# PIR.net
KiCad netlist of a schematic drawn in Altium Designer
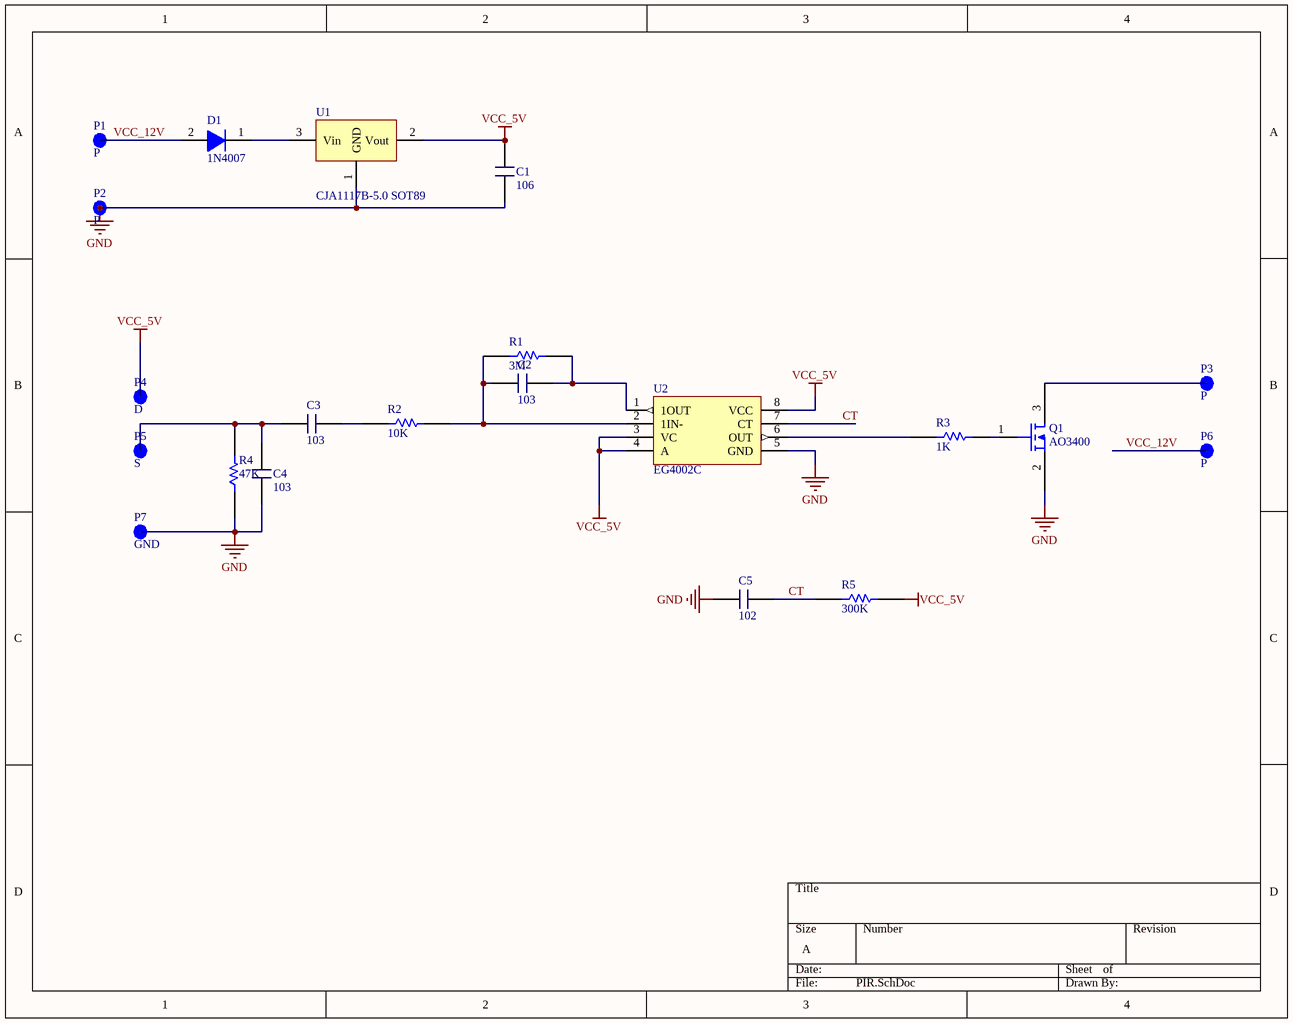
[diagram p0: PIR.SchDoc]

(export (version "E")
  (design (tool "Eeschema 10.0.6"))
  (components
    (comp (ref "C1")
      (value "106")
      (footprint "CAPC2012X12N")
      (libsource (lib "Integrated_Library1") (part "Capacitor 106"))
    )
    (comp (ref "C2")
      (value "103")
      (footprint "CAPC2012X12N")
      (libsource (lib "Integrated_Library1") (part "Capacitor 103 0603"))
    )
    (comp (ref "C3")
      (value "103")
      (footprint "CAPC2012X12N")
      (libsource (lib "Integrated_Library1") (part "Capacitor 103 0603"))
    )
    (comp (ref "C4")
      (value "103")
      (footprint "CAPC2012X12N")
      (libsource (lib "Integrated_Library1") (part "Capacitor 103 0603"))
    )
    (comp (ref "C5")
      (value "102")
      (footprint "CAPC2012X12N")
      (libsource (lib "Integrated_Library1") (part "Capacitor 102 0603"))
    )
    (comp (ref "D1")
      (value "1N4007")
      (footprint "SODFL504X244-2N")
      (description "1N4007_SMD")
      (libsource (lib "Integrated_Library1") (part "1N4007_SMD Diode"))
    )
    (comp (ref "P1") (value "P") (footprint "Point") (libsource (lib "Integrated_Library1") (part "Point")))
    (comp (ref "P2") (value "P") (footprint "Point") (libsource (lib "Integrated_Library1") (part "Point")))
    (comp (ref "P3") (value "P") (footprint "Point") (libsource (lib "Integrated_Library1") (part "Point")))
    (comp (ref "P4") (value "D") (footprint "Point") (libsource (lib "Integrated_Library1") (part "Point")))
    (comp (ref "P5") (value "S") (footprint "Point") (libsource (lib "Integrated_Library1") (part "Point")))
    (comp (ref "P6") (value "P") (footprint "Point") (libsource (lib "Integrated_Library1") (part "Point")))
    (comp (ref "P7") (value "GND") (footprint "Point") (libsource (lib "Integrated_Library1") (part "Point")))
    (comp (ref "Q1")
      (value "AO3400")
      (footprint "SOT95P278X125-3N")
      (description "AO3400  MOSFET SOT23-3")
      (libsource (lib "Integrated_Library1") (part "AO3400  MOSFET SOT23-3"))
    )
    (comp (ref "R1")
      (value "3M")
      (footprint "RESC2608X06N_0603")
      (description "Thick Film Resistors - SMD 0603 3MOHMS 5% 1/10WATT")
      (libsource (lib "Integrated_Library1") (part "3M_0603_5%"))
    )
    (comp (ref "R2")
      (value "10K")
      (footprint "RESC2608X06N_0603")
      (description "RES SMD 10K OHM 1% 1/4W 0603")
      (libsource (lib "Integrated_Library1") (part "R10k_0603_5%"))
    )
    (comp (ref "R3")
      (value "1K")
      (footprint "RESC2608X06N_0603")
      (description "Thick Film Resistors - SMD 0603 1kOHMS 5% 1/10WATT")
      (libsource (lib "Integrated_Library1") (part "1k_0603_5%"))
    )
    (comp (ref "R4")
      (value "47K")
      (footprint "RESC2608X06N_0603")
      (description "Thick Film Resistors - SMD 0603 47kOHMS 5% 1/10WATT")
      (libsource (lib "Integrated_Library1") (part "47k_0603_5%"))
    )
    (comp (ref "R5")
      (value "300K")
      (footprint "RESC2608X06N_0603")
      (description "Thick Film Resistors - SMD 0603 300kOHMS 5% 1/10WATT")
      (libsource (lib "Integrated_Library1") (part "300k_0603_5%"))
    )
    (comp (ref "U1")
      (value "CJA1117B-5.0 SOT89")
      (footprint "SOT89-150P409X160-3N")
      (description "CJA1117B-5.0 SOT89 Power IC 1A 5V_IC")
      (libsource (lib "Integrated_Library1") (part "CJA1117B-5.0 SOT89"))
    )
    (comp (ref "U2")
      (value "EG4002C")
      (footprint "TSOP127P620X155-8N")
      (description "IC PIR CONTROLLER8SOIC")
      (libsource (lib "Integrated_Library1") (part "EG4002C"))
    )
  )
  (nets
    (net (code "1") (name "/CT") (class "Default")
      (node (ref "C5") (pin "2") (pinfunction "2_2") (pintype "passive"))
      (node (ref "R5") (pin "1") (pinfunction "1_1") (pintype "passive"))
      (node (ref "U2") (pin "7") (pinfunction "CT_7") (pintype "passive"))
    )
    (net (code "2") (name "/VCC_12V") (class "Default")
      (node (ref "D1") (pin "2") (pinfunction "A_2") (pintype "passive"))
      (node (ref "P1") (pin "1") (pinfunction "1_1") (pintype "passive"))
      (node (ref "P6") (pin "1") (pinfunction "1_1") (pintype "passive"))
    )
    (net (code "3") (name "GND") (class "Default")
      (node (ref "C1") (pin "1") (pinfunction "1_1") (pintype "passive"))
      (node (ref "C4") (pin "1") (pinfunction "1_1") (pintype "passive"))
      (node (ref "C5") (pin "1") (pinfunction "1_1") (pintype "passive"))
      (node (ref "P2") (pin "1") (pinfunction "1_1") (pintype "passive"))
      (node (ref "P7") (pin "1") (pinfunction "1_1") (pintype "passive"))
      (node (ref "Q1") (pin "2") (pinfunction "S_2") (pintype "passive"))
      (node (ref "R4") (pin "1") (pinfunction "1_1") (pintype "passive"))
      (node (ref "U1") (pin "1") (pinfunction "GND_1") (pintype "power_in"))
      (node (ref "U2") (pin "5") (pinfunction "GND_5") (pintype "power_in"))
    )
    (net (code "4") (name "Net-(C3-Pad1)") (class "Default")
      (node (ref "C3") (pin "1") (pinfunction "1_1") (pintype "passive"))
      (node (ref "R2") (pin "1") (pinfunction "1_1") (pintype "passive"))
    )
    (net (code "5") (name "Net-(C3-Pad2)") (class "Default")
      (node (ref "C3") (pin "2") (pinfunction "2_2") (pintype "passive"))
      (node (ref "C4") (pin "2") (pinfunction "2_2") (pintype "passive"))
      (node (ref "P5") (pin "1") (pinfunction "1_1") (pintype "passive"))
      (node (ref "R4") (pin "2") (pinfunction "2_2") (pintype "passive"))
    )
    (net (code "6") (name "Net-(D1-C)") (class "Default")
      (node (ref "D1") (pin "1") (pinfunction "C_1") (pintype "passive"))
      (node (ref "U1") (pin "3") (pinfunction "Vin_3") (pintype "power_in"))
    )
    (net (code "7") (name "Net-(Q1-D)") (class "Default")
      (node (ref "P3") (pin "1") (pinfunction "1_1") (pintype "passive"))
      (node (ref "Q1") (pin "3") (pinfunction "D_3") (pintype "passive"))
    )
    (net (code "8") (name "Net-(Q1-G)") (class "Default")
      (node (ref "Q1") (pin "1") (pinfunction "G_1") (pintype "passive"))
      (node (ref "R3") (pin "2") (pinfunction "2_2") (pintype "passive"))
    )
    (net (code "9") (name "Net-(U2-1IN-)") (class "Default")
      (node (ref "C2") (pin "1") (pinfunction "1_1") (pintype "passive"))
      (node (ref "R1") (pin "1") (pinfunction "1_1") (pintype "passive"))
      (node (ref "R2") (pin "2") (pinfunction "2_2") (pintype "passive"))
      (node (ref "U2") (pin "2") (pinfunction "1IN-_2") (pintype "passive"))
    )
    (net (code "10") (name "Net-(U2-1OUT)") (class "Default")
      (node (ref "C2") (pin "2") (pinfunction "2_2") (pintype "passive"))
      (node (ref "R1") (pin "2") (pinfunction "2_2") (pintype "passive"))
      (node (ref "U2") (pin "1") (pinfunction "1OUT_1") (pintype "output"))
    )
    (net (code "11") (name "Net-(U2-OUT)") (class "Default")
      (node (ref "R3") (pin "1") (pinfunction "1_1") (pintype "passive"))
      (node (ref "U2") (pin "6") (pinfunction "OUT_6") (pintype "output"))
    )
    (net (code "12") (name "VCC_5V") (class "Default")
      (node (ref "C1") (pin "2") (pinfunction "2_2") (pintype "passive"))
      (node (ref "P4") (pin "1") (pinfunction "1_1") (pintype "passive"))
      (node (ref "R5") (pin "2") (pinfunction "2_2") (pintype "passive"))
      (node (ref "U1") (pin "2") (pinfunction "Vout_2") (pintype "power_in"))
      (node (ref "U2") (pin "3") (pinfunction "VC_3") (pintype "passive"))
      (node (ref "U2") (pin "4") (pinfunction "A_4") (pintype "passive"))
      (node (ref "U2") (pin "8") (pinfunction "VCC_8") (pintype "power_in"))
    )
  )
)
